# 8ch.net
KiCad netlist of a schematic drawn in EAGLE
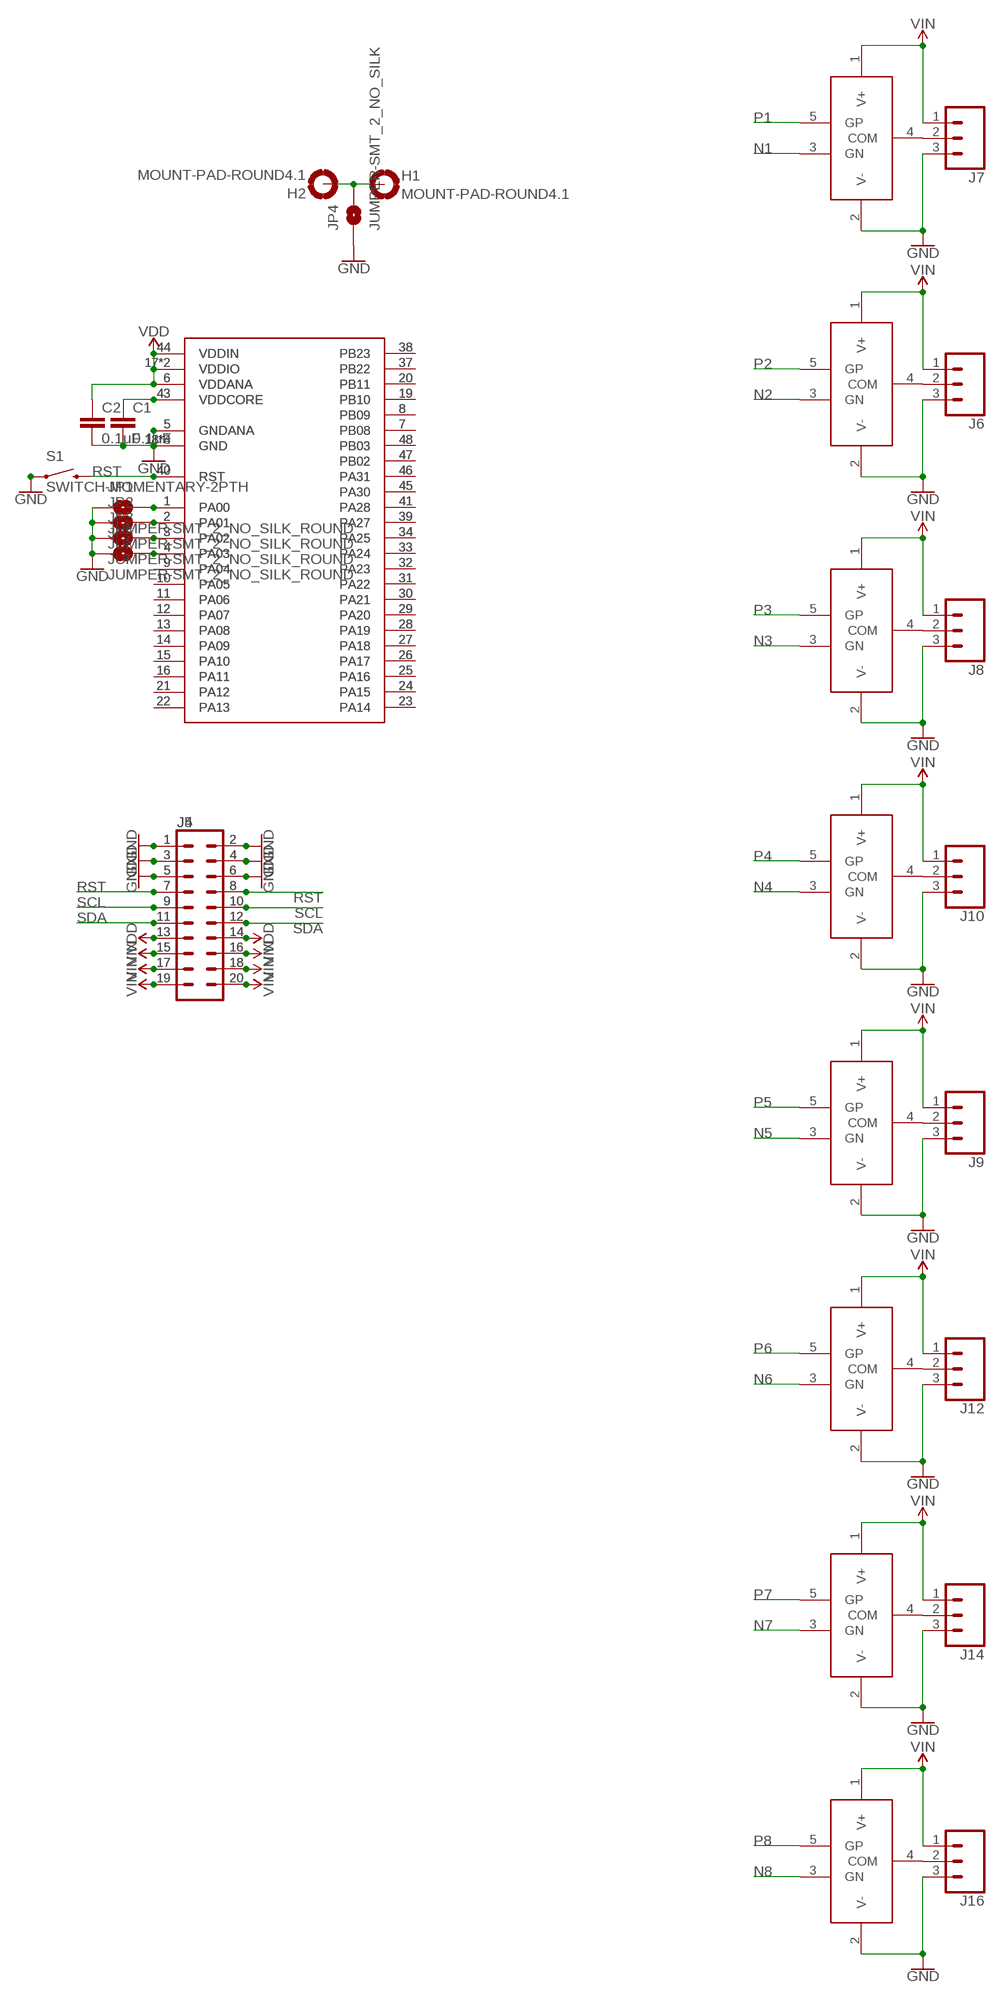
[diagram p0: schematic, sheet 1]

(export (version "E")
  (design (tool "Eeschema 10.0.6"))
  (components
    (comp (ref "C1")
      (value "0.1uF")
      (footprint "eagle-import:0603")
      (libsource (lib "eagle-import") (part "0.1UF-0603-100V-10%"))
    )
    (comp (ref "C2")
      (value "0.1uF")
      (footprint "eagle-import:0603")
      (libsource (lib "eagle-import") (part "0.1UF-0603-100V-10%"))
    )
    (comp (ref "H1")
      (value "MOUNT-PAD-ROUND4.1")
      (footprint "eagle-import:4,1-PAD")
      (libsource (lib "eagle-import") (part "MOUNT-PAD-ROUND4.1"))
    )
    (comp (ref "H2")
      (value "MOUNT-PAD-ROUND4.1")
      (footprint "eagle-import:4,1-PAD")
      (libsource (lib "eagle-import") (part "MOUNT-PAD-ROUND4.1"))
    )
    (comp (ref "J4")
      (value "CONN_10X2")
      (footprint "eagle-import:2X10")
      (libsource (lib "eagle-import") (part "CONN_10X2"))
    )
    (comp (ref "J5")
      (value "CONN_10X2")
      (footprint "eagle-import:2X10")
      (libsource (lib "eagle-import") (part "CONN_10X2"))
    )
    (comp (ref "J6")
      (value "CONN_03-SCREW-5MM")
      (footprint "eagle-import:SCREWTERMINAL-5MM-3")
      (libsource (lib "eagle-import") (part "CONN_03-SCREW-5MM"))
    )
    (comp (ref "J7")
      (value "CONN_03-SCREW-5MM")
      (footprint "eagle-import:SCREWTERMINAL-5MM-3")
      (libsource (lib "eagle-import") (part "CONN_03-SCREW-5MM"))
    )
    (comp (ref "J8")
      (value "CONN_03-SCREW-5MM")
      (footprint "eagle-import:SCREWTERMINAL-5MM-3")
      (libsource (lib "eagle-import") (part "CONN_03-SCREW-5MM"))
    )
    (comp (ref "J9")
      (value "CONN_03-SCREW-5MM")
      (footprint "eagle-import:SCREWTERMINAL-5MM-3")
      (libsource (lib "eagle-import") (part "CONN_03-SCREW-5MM"))
    )
    (comp (ref "J10")
      (value "CONN_03-SCREW-5MM")
      (footprint "eagle-import:SCREWTERMINAL-5MM-3")
      (libsource (lib "eagle-import") (part "CONN_03-SCREW-5MM"))
    )
    (comp (ref "J12")
      (value "CONN_03-SCREW-5MM")
      (footprint "eagle-import:SCREWTERMINAL-5MM-3")
      (libsource (lib "eagle-import") (part "CONN_03-SCREW-5MM"))
    )
    (comp (ref "J14")
      (value "CONN_03-SCREW-5MM")
      (footprint "eagle-import:SCREWTERMINAL-5MM-3")
      (libsource (lib "eagle-import") (part "CONN_03-SCREW-5MM"))
    )
    (comp (ref "J16")
      (value "CONN_03-SCREW-5MM")
      (footprint "eagle-import:SCREWTERMINAL-5MM-3")
      (libsource (lib "eagle-import") (part "CONN_03-SCREW-5MM"))
    )
    (comp (ref "JP1")
      (value "JUMPER-SMT_2_NO_SILK_ROUND")
      (footprint "eagle-import:SMT-JUMPER_2_NO_SILK_ROUND")
      (libsource (lib "eagle-import") (part "JUMPER-SMT_2_NO_SILK_ROUND"))
    )
    (comp (ref "JP2")
      (value "JUMPER-SMT_2_NO_SILK_ROUND")
      (footprint "eagle-import:SMT-JUMPER_2_NO_SILK_ROUND")
      (libsource (lib "eagle-import") (part "JUMPER-SMT_2_NO_SILK_ROUND"))
    )
    (comp (ref "JP3")
      (value "JUMPER-SMT_2_NO_SILK_ROUND")
      (footprint "eagle-import:SMT-JUMPER_2_NO_SILK_ROUND")
      (libsource (lib "eagle-import") (part "JUMPER-SMT_2_NO_SILK_ROUND"))
    )
    (comp (ref "JP4")
      (value "JUMPER-SMT_2_NO_SILK")
      (footprint "eagle-import:SMT-JUMPER_2_NO_SILK")
      (libsource (lib "eagle-import") (part "JUMPER-SMT_2_NO_SILK"))
    )
    (comp (ref "JP5")
      (value "JUMPER-SMT_2_NO_SILK_ROUND")
      (footprint "eagle-import:SMT-JUMPER_2_NO_SILK_ROUND")
      (libsource (lib "eagle-import") (part "JUMPER-SMT_2_NO_SILK_ROUND"))
    )
    (comp (ref "S1")
      (value "SWITCH-MOMENTARY-2PTH")
      (footprint "eagle-import:TACTILE-PTH")
      (libsource (lib "eagle-import") (part "SWITCH-MOMENTARY-2PTH"))
    )
    (comp (ref "U$1")
      (value "ATSAMD2G1A-M")
      (footprint "eagle-import:QFN48_7X7")
      (libsource (lib "eagle-import") (part "ATSAMD2G1A-M"))
    )
    (comp (ref "U$2")
      (value "COMPBJT")
      (footprint "eagle-import:SOT23-5")
      (libsource (lib "eagle-import") (part "COMPBJT"))
    )
    (comp (ref "U$3")
      (value "COMPBJT")
      (footprint "eagle-import:SOT23-5")
      (libsource (lib "eagle-import") (part "COMPBJT"))
    )
    (comp (ref "U$4")
      (value "COMPBJT")
      (footprint "eagle-import:SOT23-5")
      (libsource (lib "eagle-import") (part "COMPBJT"))
    )
    (comp (ref "U$5")
      (value "COMPBJT")
      (footprint "eagle-import:SOT23-5")
      (libsource (lib "eagle-import") (part "COMPBJT"))
    )
    (comp (ref "U$6")
      (value "COMPBJT")
      (footprint "eagle-import:SOT23-5")
      (libsource (lib "eagle-import") (part "COMPBJT"))
    )
    (comp (ref "U$7")
      (value "ATSAMD2G1A-A")
      (footprint "eagle-import:TQFP48_7X7")
      (libsource (lib "eagle-import") (part "ATSAMD2G1A-A"))
    )
    (comp (ref "U$8")
      (value "COMPBJT")
      (footprint "eagle-import:SOT23-5")
      (libsource (lib "eagle-import") (part "COMPBJT"))
    )
    (comp (ref "U$10")
      (value "COMPBJT")
      (footprint "eagle-import:SOT23-5")
      (libsource (lib "eagle-import") (part "COMPBJT"))
    )
    (comp (ref "U$12")
      (value "COMPBJT")
      (footprint "eagle-import:SOT23-5")
      (libsource (lib "eagle-import") (part "COMPBJT"))
    )
  )
  (nets
    (net (code "1") (name "/N1") (class "Default")
      (node (ref "U$3") (pin "3") (pinfunction "GN_3") (pintype "bidirectional"))
    )
    (net (code "2") (name "/N2") (class "Default")
      (node (ref "U$2") (pin "3") (pinfunction "GN_3") (pintype "bidirectional"))
    )
    (net (code "3") (name "/N3") (class "Default")
      (node (ref "U$4") (pin "3") (pinfunction "GN_3") (pintype "bidirectional"))
    )
    (net (code "4") (name "/N4") (class "Default")
      (node (ref "U$6") (pin "3") (pinfunction "GN_3") (pintype "bidirectional"))
    )
    (net (code "5") (name "/N5") (class "Default")
      (node (ref "U$5") (pin "3") (pinfunction "GN_3") (pintype "bidirectional"))
    )
    (net (code "6") (name "/N6") (class "Default")
      (node (ref "U$8") (pin "3") (pinfunction "GN_3") (pintype "bidirectional"))
    )
    (net (code "7") (name "/N7") (class "Default")
      (node (ref "U$10") (pin "3") (pinfunction "GN_3") (pintype "bidirectional"))
    )
    (net (code "8") (name "/N8") (class "Default")
      (node (ref "U$12") (pin "3") (pinfunction "GN_3") (pintype "bidirectional"))
    )
    (net (code "9") (name "/P1") (class "Default")
      (node (ref "U$3") (pin "5") (pinfunction "GP_5") (pintype "bidirectional"))
    )
    (net (code "10") (name "/P2") (class "Default")
      (node (ref "U$2") (pin "5") (pinfunction "GP_5") (pintype "bidirectional"))
    )
    (net (code "11") (name "/P3") (class "Default")
      (node (ref "U$4") (pin "5") (pinfunction "GP_5") (pintype "bidirectional"))
    )
    (net (code "12") (name "/P4") (class "Default")
      (node (ref "U$6") (pin "5") (pinfunction "GP_5") (pintype "bidirectional"))
    )
    (net (code "13") (name "/P5") (class "Default")
      (node (ref "U$5") (pin "5") (pinfunction "GP_5") (pintype "bidirectional"))
    )
    (net (code "14") (name "/P6") (class "Default")
      (node (ref "U$8") (pin "5") (pinfunction "GP_5") (pintype "bidirectional"))
    )
    (net (code "15") (name "/P7") (class "Default")
      (node (ref "U$10") (pin "5") (pinfunction "GP_5") (pintype "bidirectional"))
    )
    (net (code "16") (name "/P8") (class "Default")
      (node (ref "U$12") (pin "5") (pinfunction "GP_5") (pintype "bidirectional"))
    )
    (net (code "17") (name "/RST") (class "Default")
      (node (ref "J4") (pin "7") (pinfunction "7_7") (pintype "passive"))
      (node (ref "J4") (pin "8") (pinfunction "8_8") (pintype "passive"))
      (node (ref "J5") (pin "7") (pinfunction "7_7") (pintype "passive"))
      (node (ref "J5") (pin "8") (pinfunction "8_8") (pintype "passive"))
      (node (ref "S1") (pin "3") (pinfunction "2_3") (pintype "passive"))
      (node (ref "S1") (pin "4") (pinfunction "2_4") (pintype "passive"))
      (node (ref "U$1") (pin "40") (pinfunction "RST_40") (pintype "bidirectional"))
      (node (ref "U$7") (pin "40") (pinfunction "RST_40") (pintype "bidirectional"))
    )
    (net (code "18") (name "/SCL") (class "Default")
      (node (ref "J4") (pin "10") (pinfunction "10_10") (pintype "passive"))
      (node (ref "J4") (pin "9") (pinfunction "9_9") (pintype "passive"))
      (node (ref "J5") (pin "10") (pinfunction "10_10") (pintype "passive"))
      (node (ref "J5") (pin "9") (pinfunction "9_9") (pintype "passive"))
    )
    (net (code "19") (name "/SDA") (class "Default")
      (node (ref "J4") (pin "11") (pinfunction "11_11") (pintype "passive"))
      (node (ref "J4") (pin "12") (pinfunction "12_12") (pintype "passive"))
      (node (ref "J5") (pin "11") (pinfunction "11_11") (pintype "passive"))
      (node (ref "J5") (pin "12") (pinfunction "12_12") (pintype "passive"))
    )
    (net (code "20") (name "GND") (class "Default")
      (node (ref "C1") (pin "2") (pinfunction "2_2") (pintype "passive"))
      (node (ref "C2") (pin "2") (pinfunction "2_2") (pintype "passive"))
      (node (ref "J10") (pin "3") (pinfunction "3_3") (pintype "passive"))
      (node (ref "J12") (pin "3") (pinfunction "3_3") (pintype "passive"))
      (node (ref "J14") (pin "3") (pinfunction "3_3") (pintype "passive"))
      (node (ref "J16") (pin "3") (pinfunction "3_3") (pintype "passive"))
      (node (ref "J4") (pin "1") (pinfunction "1_1") (pintype "passive"))
      (node (ref "J4") (pin "2") (pinfunction "2_2") (pintype "passive"))
      (node (ref "J4") (pin "3") (pinfunction "3_3") (pintype "passive"))
      (node (ref "J4") (pin "4") (pinfunction "4_4") (pintype "passive"))
      (node (ref "J4") (pin "5") (pinfunction "5_5") (pintype "passive"))
      (node (ref "J4") (pin "6") (pinfunction "6_6") (pintype "passive"))
      (node (ref "J5") (pin "1") (pinfunction "1_1") (pintype "passive"))
      (node (ref "J5") (pin "2") (pinfunction "2_2") (pintype "passive"))
      (node (ref "J5") (pin "3") (pinfunction "3_3") (pintype "passive"))
      (node (ref "J5") (pin "4") (pinfunction "4_4") (pintype "passive"))
      (node (ref "J5") (pin "5") (pinfunction "5_5") (pintype "passive"))
      (node (ref "J5") (pin "6") (pinfunction "6_6") (pintype "passive"))
      (node (ref "J6") (pin "3") (pinfunction "3_3") (pintype "passive"))
      (node (ref "J7") (pin "3") (pinfunction "3_3") (pintype "passive"))
      (node (ref "J8") (pin "3") (pinfunction "3_3") (pintype "passive"))
      (node (ref "J9") (pin "3") (pinfunction "3_3") (pintype "passive"))
      (node (ref "JP1") (pin "1") (pinfunction "1_1") (pintype "passive"))
      (node (ref "JP2") (pin "1") (pinfunction "1_1") (pintype "passive"))
      (node (ref "JP3") (pin "1") (pinfunction "1_1") (pintype "passive"))
      (node (ref "JP4") (pin "1") (pinfunction "1_1") (pintype "passive"))
      (node (ref "JP5") (pin "1") (pinfunction "1_1") (pintype "passive"))
      (node (ref "S1") (pin "1") (pinfunction "1_1") (pintype "passive"))
      (node (ref "S1") (pin "2") (pinfunction "1_2") (pintype "passive"))
      (node (ref "U$1") (pin "18") (pinfunction "GND_18") (pintype "bidirectional"))
      (node (ref "U$1") (pin "35") (pinfunction "GND_35") (pintype "bidirectional"))
      (node (ref "U$1") (pin "42") (pinfunction "GND_42") (pintype "bidirectional"))
      (node (ref "U$1") (pin "5") (pinfunction "GNDANA_5") (pintype "bidirectional"))
      (node (ref "U$1") (pin "EXP") (pinfunction "GND_EXP") (pintype "bidirectional"))
      (node (ref "U$10") (pin "2") (pinfunction "V-_2") (pintype "bidirectional"))
      (node (ref "U$12") (pin "2") (pinfunction "V-_2") (pintype "bidirectional"))
      (node (ref "U$2") (pin "2") (pinfunction "V-_2") (pintype "bidirectional"))
      (node (ref "U$3") (pin "2") (pinfunction "V-_2") (pintype "bidirectional"))
      (node (ref "U$4") (pin "2") (pinfunction "V-_2") (pintype "bidirectional"))
      (node (ref "U$5") (pin "2") (pinfunction "V-_2") (pintype "bidirectional"))
      (node (ref "U$6") (pin "2") (pinfunction "V-_2") (pintype "bidirectional"))
      (node (ref "U$7") (pin "18") (pinfunction "GND_18") (pintype "bidirectional"))
      (node (ref "U$7") (pin "35") (pinfunction "GND_35") (pintype "bidirectional"))
      (node (ref "U$7") (pin "42") (pinfunction "GND_42") (pintype "bidirectional"))
      (node (ref "U$7") (pin "5") (pinfunction "GNDANA_5") (pintype "bidirectional"))
      (node (ref "U$8") (pin "2") (pinfunction "V-_2") (pintype "bidirectional"))
    )
    (net (code "21") (name "Net-(H1-MOUNT)") (class "Default")
      (node (ref "H1") (pin "B4,1") (pinfunction "MOUNT_B4,1") (pintype "passive"))
      (node (ref "H2") (pin "B4,1") (pinfunction "MOUNT_B4,1") (pintype "passive"))
      (node (ref "JP4") (pin "2") (pinfunction "2_2") (pintype "passive"))
    )
    (net (code "22") (name "Net-(U$1-PA00)") (class "Default")
      (node (ref "JP1") (pin "2") (pinfunction "2_2") (pintype "passive"))
      (node (ref "U$1") (pin "1") (pinfunction "PA00_1") (pintype "bidirectional"))
      (node (ref "U$7") (pin "1") (pinfunction "PA00_1") (pintype "bidirectional"))
    )
    (net (code "23") (name "Net-(U$1-PA01)") (class "Default")
      (node (ref "JP2") (pin "2") (pinfunction "2_2") (pintype "passive"))
      (node (ref "U$1") (pin "2") (pinfunction "PA01_2") (pintype "bidirectional"))
      (node (ref "U$7") (pin "2") (pinfunction "PA01_2") (pintype "bidirectional"))
    )
    (net (code "24") (name "Net-(U$1-PA02)") (class "Default")
      (node (ref "JP3") (pin "2") (pinfunction "2_2") (pintype "passive"))
      (node (ref "U$1") (pin "3") (pinfunction "PA02_3") (pintype "bidirectional"))
      (node (ref "U$7") (pin "3") (pinfunction "PA02_3") (pintype "bidirectional"))
    )
    (net (code "25") (name "Net-(U$1-PA03)") (class "Default")
      (node (ref "JP5") (pin "2") (pinfunction "2_2") (pintype "passive"))
      (node (ref "U$1") (pin "4") (pinfunction "PA03_4") (pintype "bidirectional"))
      (node (ref "U$7") (pin "4") (pinfunction "PA03_4") (pintype "bidirectional"))
    )
    (net (code "26") (name "Net-(U$1-PA04)") (class "Default")
      (node (ref "U$1") (pin "9") (pinfunction "PA04_9") (pintype "bidirectional"))
      (node (ref "U$7") (pin "9") (pinfunction "PA04_9") (pintype "bidirectional"))
    )
    (net (code "27") (name "Net-(U$1-PA05)") (class "Default")
      (node (ref "U$1") (pin "10") (pinfunction "PA05_10") (pintype "bidirectional"))
      (node (ref "U$7") (pin "10") (pinfunction "PA05_10") (pintype "bidirectional"))
    )
    (net (code "28") (name "Net-(U$1-PA06)") (class "Default")
      (node (ref "U$1") (pin "11") (pinfunction "PA06_11") (pintype "bidirectional"))
      (node (ref "U$7") (pin "11") (pinfunction "PA06_11") (pintype "bidirectional"))
    )
    (net (code "29") (name "Net-(U$1-PA07)") (class "Default")
      (node (ref "U$1") (pin "12") (pinfunction "PA07_12") (pintype "bidirectional"))
      (node (ref "U$7") (pin "12") (pinfunction "PA07_12") (pintype "bidirectional"))
    )
    (net (code "30") (name "Net-(U$1-PA08)") (class "Default")
      (node (ref "U$1") (pin "13") (pinfunction "PA08_13") (pintype "bidirectional"))
      (node (ref "U$7") (pin "13") (pinfunction "PA08_13") (pintype "bidirectional"))
    )
    (net (code "31") (name "Net-(U$1-PA09)") (class "Default")
      (node (ref "U$1") (pin "14") (pinfunction "PA09_14") (pintype "bidirectional"))
      (node (ref "U$7") (pin "14") (pinfunction "PA09_14") (pintype "bidirectional"))
    )
    (net (code "32") (name "Net-(U$1-PA10)") (class "Default")
      (node (ref "U$1") (pin "15") (pinfunction "PA10_15") (pintype "bidirectional"))
      (node (ref "U$7") (pin "15") (pinfunction "PA10_15") (pintype "bidirectional"))
    )
    (net (code "33") (name "Net-(U$1-PA11)") (class "Default")
      (node (ref "U$1") (pin "16") (pinfunction "PA11_16") (pintype "bidirectional"))
      (node (ref "U$7") (pin "16") (pinfunction "PA11_16") (pintype "bidirectional"))
    )
    (net (code "34") (name "Net-(U$1-PA12)") (class "Default")
      (node (ref "U$1") (pin "21") (pinfunction "PA12_21") (pintype "bidirectional"))
      (node (ref "U$7") (pin "21") (pinfunction "PA12_21") (pintype "bidirectional"))
    )
    (net (code "35") (name "Net-(U$1-PA13)") (class "Default")
      (node (ref "U$1") (pin "22") (pinfunction "PA13_22") (pintype "bidirectional"))
      (node (ref "U$7") (pin "22") (pinfunction "PA13_22") (pintype "bidirectional"))
    )
    (net (code "36") (name "Net-(U$1-PA14)") (class "Default")
      (node (ref "U$1") (pin "23") (pinfunction "PA14_23") (pintype "bidirectional"))
      (node (ref "U$7") (pin "23") (pinfunction "PA14_23") (pintype "bidirectional"))
    )
    (net (code "37") (name "Net-(U$1-PA15)") (class "Default")
      (node (ref "U$1") (pin "24") (pinfunction "PA15_24") (pintype "bidirectional"))
      (node (ref "U$7") (pin "24") (pinfunction "PA15_24") (pintype "bidirectional"))
    )
    (net (code "38") (name "Net-(U$1-PA16)") (class "Default")
      (node (ref "U$1") (pin "25") (pinfunction "PA16_25") (pintype "bidirectional"))
      (node (ref "U$7") (pin "25") (pinfunction "PA16_25") (pintype "bidirectional"))
    )
    (net (code "39") (name "Net-(U$1-PA17)") (class "Default")
      (node (ref "U$1") (pin "26") (pinfunction "PA17_26") (pintype "bidirectional"))
      (node (ref "U$7") (pin "26") (pinfunction "PA17_26") (pintype "bidirectional"))
    )
    (net (code "40") (name "Net-(U$1-PA18)") (class "Default")
      (node (ref "U$1") (pin "27") (pinfunction "PA18_27") (pintype "bidirectional"))
      (node (ref "U$7") (pin "27") (pinfunction "PA18_27") (pintype "bidirectional"))
    )
    (net (code "41") (name "Net-(U$1-PA19)") (class "Default")
      (node (ref "U$1") (pin "28") (pinfunction "PA19_28") (pintype "bidirectional"))
      (node (ref "U$7") (pin "28") (pinfunction "PA19_28") (pintype "bidirectional"))
    )
    (net (code "42") (name "Net-(U$1-PA20)") (class "Default")
      (node (ref "U$1") (pin "29") (pinfunction "PA20_29") (pintype "bidirectional"))
      (node (ref "U$7") (pin "29") (pinfunction "PA20_29") (pintype "bidirectional"))
    )
    (net (code "43") (name "Net-(U$1-PA21)") (class "Default")
      (node (ref "U$1") (pin "30") (pinfunction "PA21_30") (pintype "bidirectional"))
      (node (ref "U$7") (pin "30") (pinfunction "PA21_30") (pintype "bidirectional"))
    )
    (net (code "44") (name "Net-(U$1-PA22)") (class "Default")
      (node (ref "U$1") (pin "31") (pinfunction "PA22_31") (pintype "bidirectional"))
      (node (ref "U$7") (pin "31") (pinfunction "PA22_31") (pintype "bidirectional"))
    )
    (net (code "45") (name "Net-(U$1-PA23)") (class "Default")
      (node (ref "U$1") (pin "32") (pinfunction "PA23_32") (pintype "bidirectional"))
      (node (ref "U$7") (pin "32") (pinfunction "PA23_32") (pintype "bidirectional"))
    )
    (net (code "46") (name "Net-(U$1-PA24)") (class "Default")
      (node (ref "U$1") (pin "33") (pinfunction "PA24_33") (pintype "bidirectional"))
      (node (ref "U$7") (pin "33") (pinfunction "PA24_33") (pintype "bidirectional"))
    )
    (net (code "47") (name "Net-(U$1-PA25)") (class "Default")
      (node (ref "U$1") (pin "34") (pinfunction "PA25_34") (pintype "bidirectional"))
      (node (ref "U$7") (pin "34") (pinfunction "PA25_34") (pintype "bidirectional"))
    )
    (net (code "48") (name "Net-(U$1-PA27)") (class "Default")
      (node (ref "U$1") (pin "39") (pinfunction "PA27_39") (pintype "bidirectional"))
      (node (ref "U$7") (pin "39") (pinfunction "PA27_39") (pintype "bidirectional"))
    )
    (net (code "49") (name "Net-(U$1-PA28)") (class "Default")
      (node (ref "U$1") (pin "41") (pinfunction "PA28_41") (pintype "bidirectional"))
      (node (ref "U$7") (pin "41") (pinfunction "PA28_41") (pintype "bidirectional"))
    )
    (net (code "50") (name "Net-(U$1-PA30)") (class "Default")
      (node (ref "U$1") (pin "45") (pinfunction "PA30_45") (pintype "bidirectional"))
      (node (ref "U$7") (pin "45") (pinfunction "PA30_45") (pintype "bidirectional"))
    )
    (net (code "51") (name "Net-(U$1-PA31)") (class "Default")
      (node (ref "U$1") (pin "46") (pinfunction "PA31_46") (pintype "bidirectional"))
      (node (ref "U$7") (pin "46") (pinfunction "PA31_46") (pintype "bidirectional"))
    )
    (net (code "52") (name "Net-(U$1-PB02)") (class "Default")
      (node (ref "U$1") (pin "47") (pinfunction "PB02_47") (pintype "bidirectional"))
      (node (ref "U$7") (pin "47") (pinfunction "PB02_47") (pintype "bidirectional"))
    )
    (net (code "53") (name "Net-(U$1-PB03)") (class "Default")
      (node (ref "U$1") (pin "48") (pinfunction "PB03_48") (pintype "bidirectional"))
      (node (ref "U$7") (pin "48") (pinfunction "PB03_48") (pintype "bidirectional"))
    )
    (net (code "54") (name "Net-(U$1-PB08)") (class "Default")
      (node (ref "U$1") (pin "7") (pinfunction "PB08_7") (pintype "bidirectional"))
      (node (ref "U$7") (pin "7") (pinfunction "PB08_7") (pintype "bidirectional"))
    )
    (net (code "55") (name "Net-(U$1-PB09)") (class "Default")
      (node (ref "U$1") (pin "8") (pinfunction "PB09_8") (pintype "bidirectional"))
      (node (ref "U$7") (pin "8") (pinfunction "PB09_8") (pintype "bidirectional"))
    )
    (net (code "56") (name "Net-(U$1-PB10)") (class "Default")
      (node (ref "U$1") (pin "19") (pinfunction "PB10_19") (pintype "bidirectional"))
      (node (ref "U$7") (pin "19") (pinfunction "PB10_19") (pintype "bidirectional"))
    )
    (net (code "57") (name "Net-(U$1-PB11)") (class "Default")
      (node (ref "U$1") (pin "20") (pinfunction "PB11_20") (pintype "bidirectional"))
      (node (ref "U$7") (pin "20") (pinfunction "PB11_20") (pintype "bidirectional"))
    )
    (net (code "58") (name "Net-(U$1-PB22)") (class "Default")
      (node (ref "U$1") (pin "37") (pinfunction "PB22_37") (pintype "bidirectional"))
      (node (ref "U$7") (pin "37") (pinfunction "PB22_37") (pintype "bidirectional"))
    )
    (net (code "59") (name "Net-(U$1-PB23)") (class "Default")
      (node (ref "U$1") (pin "38") (pinfunction "PB23_38") (pintype "bidirectional"))
      (node (ref "U$7") (pin "38") (pinfunction "PB23_38") (pintype "bidirectional"))
    )
    (net (code "60") (name "Net-(U$1-VDDCORE)") (class "Default")
      (node (ref "C1") (pin "1") (pinfunction "1_1") (pintype "passive"))
      (node (ref "U$1") (pin "43") (pinfunction "VDDCORE_43") (pintype "bidirectional"))
      (node (ref "U$7") (pin "43") (pinfunction "VDDCORE_43") (pintype "bidirectional"))
    )
    (net (code "61") (name "Net-(U$2-COM)") (class "Default")
      (node (ref "J6") (pin "2") (pinfunction "2_2") (pintype "passive"))
      (node (ref "U$2") (pin "4") (pinfunction "COM_4") (pintype "bidirectional"))
    )
    (net (code "62") (name "Net-(U$3-COM)") (class "Default")
      (node (ref "J7") (pin "2") (pinfunction "2_2") (pintype "passive"))
      (node (ref "U$3") (pin "4") (pinfunction "COM_4") (pintype "bidirectional"))
    )
    (net (code "63") (name "Net-(U$4-COM)") (class "Default")
      (node (ref "J8") (pin "2") (pinfunction "2_2") (pintype "passive"))
      (node (ref "U$4") (pin "4") (pinfunction "COM_4") (pintype "bidirectional"))
    )
    (net (code "64") (name "Net-(U$5-COM)") (class "Default")
      (node (ref "J9") (pin "2") (pinfunction "2_2") (pintype "passive"))
      (node (ref "U$5") (pin "4") (pinfunction "COM_4") (pintype "bidirectional"))
    )
    (net (code "65") (name "Net-(U$6-COM)") (class "Default")
      (node (ref "J10") (pin "2") (pinfunction "2_2") (pintype "passive"))
      (node (ref "U$6") (pin "4") (pinfunction "COM_4") (pintype "bidirectional"))
    )
    (net (code "66") (name "Net-(U$8-COM)") (class "Default")
      (node (ref "J12") (pin "2") (pinfunction "2_2") (pintype "passive"))
      (node (ref "U$8") (pin "4") (pinfunction "COM_4") (pintype "bidirectional"))
    )
    (net (code "67") (name "Net-(U$10-COM)") (class "Default")
      (node (ref "J14") (pin "2") (pinfunction "2_2") (pintype "passive"))
      (node (ref "U$10") (pin "4") (pinfunction "COM_4") (pintype "bidirectional"))
    )
    (net (code "68") (name "Net-(U$12-COM)") (class "Default")
      (node (ref "J16") (pin "2") (pinfunction "2_2") (pintype "passive"))
      (node (ref "U$12") (pin "4") (pinfunction "COM_4") (pintype "bidirectional"))
    )
    (net (code "69") (name "VDD") (class "Default")
      (node (ref "C2") (pin "1") (pinfunction "1_1") (pintype "passive"))
      (node (ref "J4") (pin "13") (pinfunction "13_13") (pintype "passive"))
      (node (ref "J4") (pin "14") (pinfunction "14_14") (pintype "passive"))
      (node (ref "J5") (pin "13") (pinfunction "13_13") (pintype "passive"))
      (node (ref "J5") (pin "14") (pinfunction "14_14") (pintype "passive"))
      (node (ref "U$1") (pin "17") (pinfunction "VDDIO_17") (pintype "bidirectional"))
      (node (ref "U$1") (pin "36") (pinfunction "VDDIO_36") (pintype "bidirectional"))
      (node (ref "U$1") (pin "44") (pinfunction "VDDIN_44") (pintype "bidirectional"))
      (node (ref "U$1") (pin "6") (pinfunction "VDDANA_6") (pintype "bidirectional"))
      (node (ref "U$7") (pin "17") (pinfunction "VDDIO_17") (pintype "bidirectional"))
      (node (ref "U$7") (pin "36") (pinfunction "VDDIO_36") (pintype "bidirectional"))
      (node (ref "U$7") (pin "44") (pinfunction "VDDIN_44") (pintype "bidirectional"))
      (node (ref "U$7") (pin "6") (pinfunction "VDDANA_6") (pintype "bidirectional"))
    )
    (net (code "70") (name "VIN") (class "Default")
      (node (ref "J10") (pin "1") (pinfunction "1_1") (pintype "passive"))
      (node (ref "J12") (pin "1") (pinfunction "1_1") (pintype "passive"))
      (node (ref "J14") (pin "1") (pinfunction "1_1") (pintype "passive"))
      (node (ref "J16") (pin "1") (pinfunction "1_1") (pintype "passive"))
      (node (ref "J4") (pin "15") (pinfunction "15_15") (pintype "passive"))
      (node (ref "J4") (pin "16") (pinfunction "16_16") (pintype "passive"))
      (node (ref "J4") (pin "17") (pinfunction "17_17") (pintype "passive"))
      (node (ref "J4") (pin "18") (pinfunction "18_18") (pintype "passive"))
      (node (ref "J4") (pin "19") (pinfunction "19_19") (pintype "passive"))
      (node (ref "J4") (pin "20") (pinfunction "20_20") (pintype "passive"))
      (node (ref "J5") (pin "15") (pinfunction "15_15") (pintype "passive"))
      (node (ref "J5") (pin "16") (pinfunction "16_16") (pintype "passive"))
      (node (ref "J5") (pin "17") (pinfunction "17_17") (pintype "passive"))
      (node (ref "J5") (pin "18") (pinfunction "18_18") (pintype "passive"))
      (node (ref "J5") (pin "19") (pinfunction "19_19") (pintype "passive"))
      (node (ref "J5") (pin "20") (pinfunction "20_20") (pintype "passive"))
      (node (ref "J6") (pin "1") (pinfunction "1_1") (pintype "passive"))
      (node (ref "J7") (pin "1") (pinfunction "1_1") (pintype "passive"))
      (node (ref "J8") (pin "1") (pinfunction "1_1") (pintype "passive"))
      (node (ref "J9") (pin "1") (pinfunction "1_1") (pintype "passive"))
      (node (ref "U$10") (pin "1") (pinfunction "V+_1") (pintype "bidirectional"))
      (node (ref "U$12") (pin "1") (pinfunction "V+_1") (pintype "bidirectional"))
      (node (ref "U$2") (pin "1") (pinfunction "V+_1") (pintype "bidirectional"))
      (node (ref "U$3") (pin "1") (pinfunction "V+_1") (pintype "bidirectional"))
      (node (ref "U$4") (pin "1") (pinfunction "V+_1") (pintype "bidirectional"))
      (node (ref "U$5") (pin "1") (pinfunction "V+_1") (pintype "bidirectional"))
      (node (ref "U$6") (pin "1") (pinfunction "V+_1") (pintype "bidirectional"))
      (node (ref "U$8") (pin "1") (pinfunction "V+_1") (pintype "bidirectional"))
    )
  )
)
